# untitled.net
KiCad netlist of a schematic drawn in EAGLE
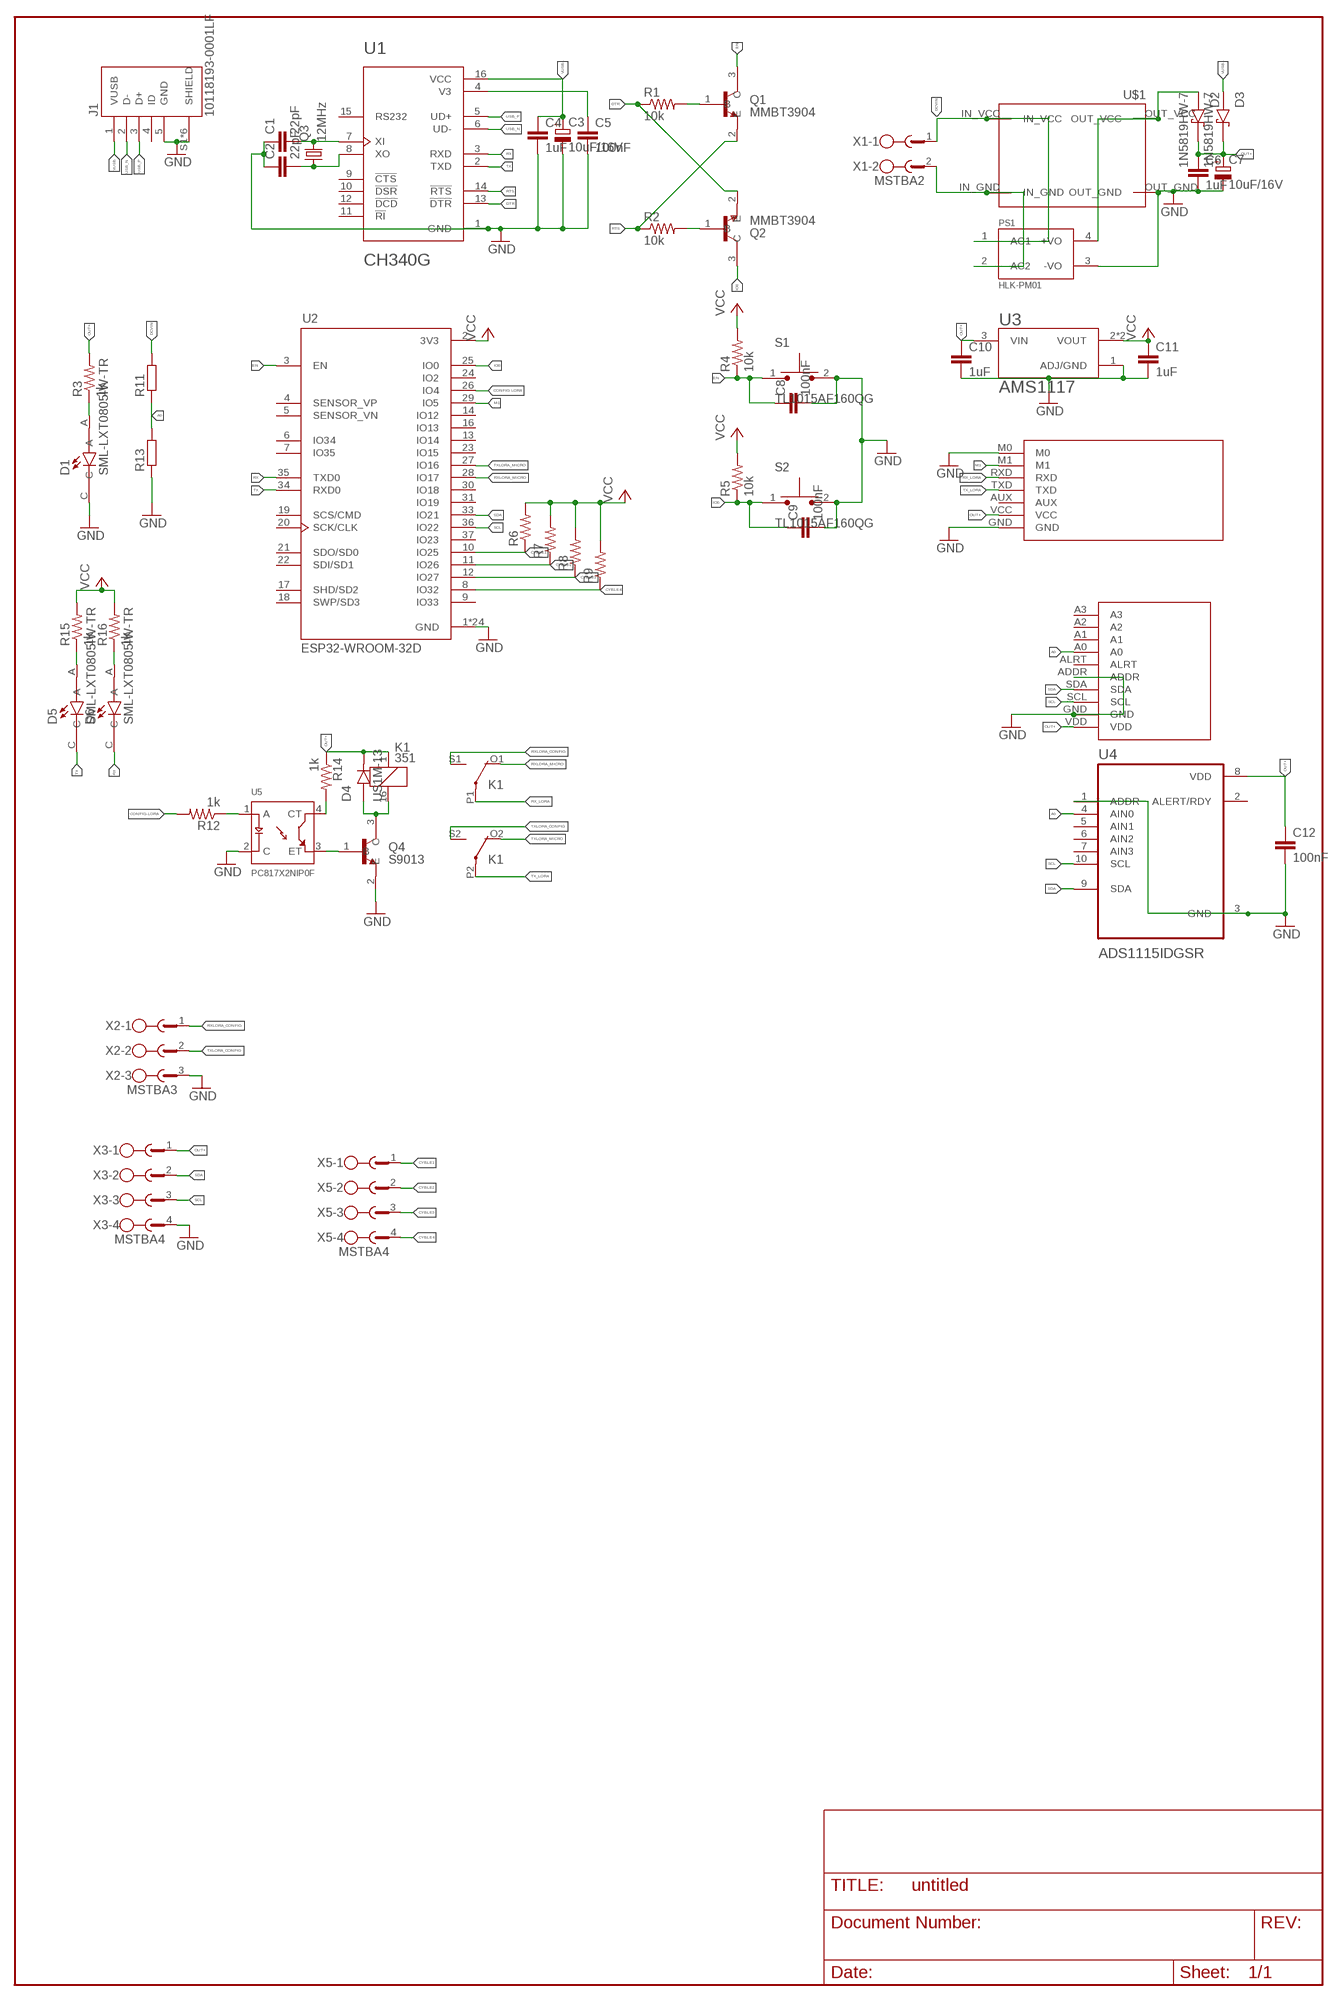
[diagram p0: schematic, sheet 1]

(export (version "E")
  (design (tool "Eeschema 10.0.6"))
  (components
    (comp (ref "ADS1")
      (value "ADS1115")
      (footprint "eagle-import:ADS1115")
      (libsource (lib "eagle-import") (part "ADS1115"))
    )
    (comp (ref "C1")
      (value "22pF")
      (footprint "eagle-import:C0805K")
      (libsource (lib "eagle-import") (part "C-EUC0805K"))
    )
    (comp (ref "C2")
      (value "22pF")
      (footprint "eagle-import:C0805K")
      (libsource (lib "eagle-import") (part "C-EUC0805K"))
    )
    (comp (ref "C3")
      (value "10uF/16V")
      (footprint "eagle-import:153CLV-0505")
      (libsource (lib "eagle-import") (part "CPOL-EU153CLV-0505"))
    )
    (comp (ref "C4")
      (value "1uF")
      (footprint "eagle-import:C0805K")
      (libsource (lib "eagle-import") (part "C-EUC0805K"))
    )
    (comp (ref "C5")
      (value "100nF")
      (footprint "eagle-import:C0805K")
      (libsource (lib "eagle-import") (part "C-EUC0805K"))
    )
    (comp (ref "C6")
      (value "1uF")
      (footprint "eagle-import:C0805K")
      (libsource (lib "eagle-import") (part "C-EUC0805K"))
    )
    (comp (ref "C7")
      (value "10uF/16V")
      (footprint "eagle-import:153CLV-0505")
      (libsource (lib "eagle-import") (part "CPOL-EU153CLV-0505"))
    )
    (comp (ref "C8")
      (value "100nF")
      (footprint "eagle-import:C0805K")
      (libsource (lib "eagle-import") (part "C-EUC0805K"))
    )
    (comp (ref "C9")
      (value "100nF")
      (footprint "eagle-import:C0805K")
      (libsource (lib "eagle-import") (part "C-EUC0805K"))
    )
    (comp (ref "C10")
      (value "1uF")
      (footprint "eagle-import:C0805K")
      (libsource (lib "eagle-import") (part "C-EUC0805K"))
    )
    (comp (ref "C11")
      (value "1uF")
      (footprint "eagle-import:C0805K")
      (libsource (lib "eagle-import") (part "C-EUC0805K"))
    )
    (comp (ref "C12")
      (value "100nF")
      (footprint "eagle-import:C0805K")
      (libsource (lib "eagle-import") (part "C-EUC0805K"))
    )
    (comp (ref "D1")
      (value "SML-LXT0805IW-TR")
      (footprint "eagle-import:LEDC2012X120N")
      (fields (field (name "MF") "Lumex Opto/Components"))
      (libsource (lib "eagle-import") (part "SML-LXT0805IW-TR"))
    )
    (comp (ref "D2")
      (value "1N5819HW-7")
      (footprint "eagle-import:SOD3715X145N")
      (fields (field (name "MF") "Diodes Inc."))
      (libsource (lib "eagle-import") (part "1N5819HW-7"))
    )
    (comp (ref "D3")
      (value "1N5819HW-7")
      (footprint "eagle-import:SOD3715X145N")
      (fields (field (name "MF") "Diodes Inc."))
      (libsource (lib "eagle-import") (part "1N5819HW-7"))
    )
    (comp (ref "D4")
      (value "US1M-13")
      (footprint "eagle-import:DIOM5226X240N")
      (fields (field (name "MF") "Diodes Incorporated"))
      (libsource (lib "eagle-import") (part "US1M-13"))
    )
    (comp (ref "D5")
      (value "SML-LXT0805IW-TR")
      (footprint "eagle-import:LEDC2012X120N")
      (fields (field (name "MF") "Lumex Opto/Components"))
      (libsource (lib "eagle-import") (part "SML-LXT0805IW-TR"))
    )
    (comp (ref "D6")
      (value "SML-LXT0805IW-TR")
      (footprint "eagle-import:LEDC2012X120N")
      (fields (field (name "MF") "Lumex Opto/Components"))
      (libsource (lib "eagle-import") (part "SML-LXT0805IW-TR"))
    )
    (comp (ref "EBYTEE220-900T22D1")
      (value "EBYTEE220-900T22D")
      (footprint "eagle-import:EBYTEE220-900T22D")
      (libsource (lib "eagle-import") (part "EBYTEE220-900T22D"))
    )
    (comp (ref "J1")
      (value "10118193-0001LF")
      (footprint "eagle-import:FCI_10118193-0001LF")
      (fields (field (name "MF") "FCI"))
      (libsource (lib "eagle-import") (part "10118193-0001LF"))
    )
    (comp (ref "K1")
      (value "351")
      (footprint "eagle-import:351")
      (libsource (lib "eagle-import") (part "351"))
    )
    (comp (ref "PS1")
      (value "HLK-PM01")
      (footprint "eagle-import:CONV_HLK-PM01")
      (fields (field (name "MF") "Hi-link") (field (name "MP") "hlk-pm01"))
      (libsource (lib "eagle-import") (part "HLK-PM01"))
    )
    (comp (ref "Q1")
      (value "MMBT3904")
      (footprint "eagle-import:SOT95P240X120-3N")
      (fields (field (name "MF") "ON Semiconductor"))
      (libsource (lib "eagle-import") (part "MMBT3904"))
    )
    (comp (ref "Q2")
      (value "MMBT3904")
      (footprint "eagle-import:SOT95P240X120-3N")
      (fields (field (name "MF") "ON Semiconductor"))
      (libsource (lib "eagle-import") (part "MMBT3904"))
    )
    (comp (ref "Q3")
      (value "12MHz")
      (footprint "eagle-import:SM49")
      (libsource (lib "eagle-import") (part "CRYSTALSM49"))
    )
    (comp (ref "Q4")
      (value "S9013")
      (footprint "eagle-import:SOT95P240X120-3N")
      (fields (field (name "MF") "JCET"))
      (libsource (lib "eagle-import") (part "S9013"))
    )
    (comp (ref "R1")
      (value "10k")
      (footprint "eagle-import:M0805")
      (libsource (lib "eagle-import") (part "R-US_M0805"))
    )
    (comp (ref "R2")
      (value "10k")
      (footprint "eagle-import:M0805")
      (libsource (lib "eagle-import") (part "R-US_M0805"))
    )
    (comp (ref "R3")
      (value "1k")
      (footprint "eagle-import:M0805")
      (libsource (lib "eagle-import") (part "R-US_M0805"))
    )
    (comp (ref "R4")
      (value "10k")
      (footprint "eagle-import:M0805")
      (libsource (lib "eagle-import") (part "R-US_M0805"))
    )
    (comp (ref "R5")
      (value "10k")
      (footprint "eagle-import:M0805")
      (libsource (lib "eagle-import") (part "R-US_M0805"))
    )
    (comp (ref "R6")
      (value "R-US_M0805")
      (footprint "eagle-import:M0805")
      (libsource (lib "eagle-import") (part "R-US_M0805"))
    )
    (comp (ref "R7")
      (value "R-US_M0805")
      (footprint "eagle-import:M0805")
      (libsource (lib "eagle-import") (part "R-US_M0805"))
    )
    (comp (ref "R8")
      (value "R-US_M0805")
      (footprint "eagle-import:M0805")
      (libsource (lib "eagle-import") (part "R-US_M0805"))
    )
    (comp (ref "R9")
      (value "R-US_M0805")
      (footprint "eagle-import:M0805")
      (libsource (lib "eagle-import") (part "R-US_M0805"))
    )
    (comp (ref "R11")
      (value "R-EU_0207/12")
      (footprint "eagle-import:0207_12")
      (libsource (lib "eagle-import") (part "R-EU_0207/12"))
    )
    (comp (ref "R12")
      (value "1k")
      (footprint "eagle-import:M0805")
      (libsource (lib "eagle-import") (part "R-US_M0805"))
    )
    (comp (ref "R13")
      (value "R-EU_0207/12")
      (footprint "eagle-import:0207_12")
      (libsource (lib "eagle-import") (part "R-EU_0207/12"))
    )
    (comp (ref "R14")
      (value "1k")
      (footprint "eagle-import:M0805")
      (libsource (lib "eagle-import") (part "R-US_M0805"))
    )
    (comp (ref "R15")
      (value "1k")
      (footprint "eagle-import:M0805")
      (libsource (lib "eagle-import") (part "R-US_M0805"))
    )
    (comp (ref "R16")
      (value "1k")
      (footprint "eagle-import:M0805")
      (libsource (lib "eagle-import") (part "R-US_M0805"))
    )
    (comp (ref "S1")
      (value "TL1015AF160QG")
      (footprint "eagle-import:SW_TL1015AF160QG")
      (fields (field (name "MF") "E-Switch"))
      (libsource (lib "eagle-import") (part "TL1015AF160QG"))
    )
    (comp (ref "S2")
      (value "TL1015AF160QG")
      (footprint "eagle-import:SW_TL1015AF160QG")
      (fields (field (name "MF") "E-Switch"))
      (libsource (lib "eagle-import") (part "TL1015AF160QG"))
    )
    (comp (ref "U$1")
      (value "STEPDOWN_SY8205")
      (footprint "eagle-import:STEPDOWN_SY8205")
      (libsource (lib "eagle-import") (part "STEPDOWN_SY8205"))
    )
    (comp (ref "U1")
      (value "CH340G")
      (footprint "eagle-import:SOIC127P600X180-16N")
      (fields (field (name "MF") "WCH") (field (name "MP") "Ch340G"))
      (libsource (lib "eagle-import") (part "CH340G"))
    )
    (comp (ref "U2")
      (value "ESP32-WROOM-32D")
      (footprint "eagle-import:MODULE_ESP32-WROOM-32D")
      (fields (field (name "MF") "Espressif Systems"))
      (libsource (lib "eagle-import") (part "ESP32-WROOM-32D"))
    )
    (comp (ref "U3")
      (value "AMS1117")
      (footprint "eagle-import:SOT229P700X180-4N")
      (fields (field (name "MF") "Advanced Monolithic Systems"))
      (libsource (lib "eagle-import") (part "AMS1117"))
    )
    (comp (ref "U4")
      (value "ADS1115IDGSR")
      (footprint "eagle-import:SOP50P490X110-10N")
      (fields (field (name "MF") "Texas Instruments"))
      (libsource (lib "eagle-import") (part "ADS1115IDGSR"))
    )
    (comp (ref "U5")
      (value "PC817X2NIP0F")
      (footprint "eagle-import:SOT254P975X400-4N")
      (fields (field (name "MF") "Sharp Microelectronics"))
      (libsource (lib "eagle-import") (part "PC817X2NIP0F"))
    )
    (comp (ref "X1")
      (value "MSTBA2")
      (footprint "eagle-import:MSTBA2")
      (fields (field (name "MF") "FARNELL") (field (name "MPN") "1757242"))
      (libsource (lib "eagle-import") (part "MSTBA2"))
    )
    (comp (ref "X2")
      (value "MSTBA3")
      (footprint "eagle-import:MSTBA3")
      (fields (field (name "MF") "FARNELL") (field (name "MPN") "1757255"))
      (libsource (lib "eagle-import") (part "MSTBA3"))
    )
    (comp (ref "X3")
      (value "MSTBA4")
      (footprint "eagle-import:MSTBA4")
      (fields (field (name "MF") "FARNELL") (field (name "MPN") "1757268"))
      (libsource (lib "eagle-import") (part "MSTBA4"))
    )
    (comp (ref "X5")
      (value "MSTBA4")
      (footprint "eagle-import:MSTBA4")
      (fields (field (name "MF") "FARNELL") (field (name "MPN") "1757268"))
      (libsource (lib "eagle-import") (part "MSTBA4"))
    )
  )
  (nets
    (net (code "1") (name "A0") (class "Default")
      (node (ref "ADS1") (pin "A0") (pinfunction "A0_A0") (pintype "bidirectional"))
      (node (ref "R11") (pin "1") (pinfunction "1_1") (pintype "passive"))
      (node (ref "R13") (pin "2") (pinfunction "2_2") (pintype "passive"))
      (node (ref "U4") (pin "4") (pinfunction "AIN0_4") (pintype "input"))
    )
    (net (code "2") (name "CONFIG-LORA") (class "Default")
      (node (ref "R12") (pin "2") (pinfunction "2_2") (pintype "passive"))
      (node (ref "U2") (pin "26") (pinfunction "IO4_26") (pintype "bidirectional"))
    )
    (net (code "3") (name "CYBLE1") (class "Default")
      (node (ref "R6") (pin "1") (pinfunction "1_1") (pintype "passive"))
      (node (ref "U2") (pin "10") (pinfunction "IO25_10") (pintype "bidirectional"))
      (node (ref "X5") (pin "1") (pinfunction "1_1") (pintype "passive"))
    )
    (net (code "4") (name "CYBLE2") (class "Default")
      (node (ref "R7") (pin "1") (pinfunction "1_1") (pintype "passive"))
      (node (ref "U2") (pin "11") (pinfunction "IO26_11") (pintype "bidirectional"))
      (node (ref "X5") (pin "2") (pinfunction "1_2") (pintype "passive"))
    )
    (net (code "5") (name "CYBLE3") (class "Default")
      (node (ref "R8") (pin "1") (pinfunction "1_1") (pintype "passive"))
      (node (ref "U2") (pin "12") (pinfunction "IO27_12") (pintype "bidirectional"))
      (node (ref "X5") (pin "3") (pinfunction "1_3") (pintype "passive"))
    )
    (net (code "6") (name "CYBLE4") (class "Default")
      (node (ref "R9") (pin "1") (pinfunction "1_1") (pintype "passive"))
      (node (ref "U2") (pin "8") (pinfunction "IO32_8") (pintype "bidirectional"))
      (node (ref "X5") (pin "4") (pinfunction "1_4") (pintype "passive"))
    )
    (net (code "7") (name "DCVIN") (class "Default")
      (node (ref "PS1") (pin "1") (pinfunction "AC1_1") (pintype "input"))
      (node (ref "R11") (pin "2") (pinfunction "2_2") (pintype "passive"))
      (node (ref "U$1") (pin "IN_VCC") (pinfunction "IN_VCC_IN_VCC") (pintype "bidirectional"))
      (node (ref "X1") (pin "1") (pinfunction "1_1") (pintype "passive"))
    )
    (net (code "8") (name "DTR") (class "Default")
      (node (ref "Q2") (pin "2") (pinfunction "E_2") (pintype "passive"))
      (node (ref "R1") (pin "1") (pinfunction "1_1") (pintype "passive"))
      (node (ref "U1") (pin "13") (pinfunction "~{DTR}_13") (pintype "output"))
    )
    (net (code "9") (name "EN") (class "Default")
      (node (ref "C8") (pin "1") (pinfunction "1_1") (pintype "passive"))
      (node (ref "Q1") (pin "3") (pinfunction "C_3") (pintype "passive"))
      (node (ref "R4") (pin "1") (pinfunction "1_1") (pintype "passive"))
      (node (ref "S1") (pin "1") (pinfunction "1_1") (pintype "passive"))
      (node (ref "U2") (pin "3") (pinfunction "EN_3") (pintype "input"))
    )
    (net (code "10") (name "GND") (class "Default")
      (node (ref "ADS1") (pin "ADDR") (pinfunction "ADDR_ADDR") (pintype "bidirectional"))
      (node (ref "ADS1") (pin "GND") (pinfunction "GND_GND") (pintype "bidirectional"))
      (node (ref "C1") (pin "1") (pinfunction "1_1") (pintype "passive"))
      (node (ref "C10") (pin "2") (pinfunction "2_2") (pintype "passive"))
      (node (ref "C11") (pin "2") (pinfunction "2_2") (pintype "passive"))
      (node (ref "C12") (pin "2") (pinfunction "2_2") (pintype "passive"))
      (node (ref "C2") (pin "1") (pinfunction "1_1") (pintype "passive"))
      (node (ref "C3") (pin "-") (pinfunction "-_-") (pintype "passive"))
      (node (ref "C4") (pin "2") (pinfunction "2_2") (pintype "passive"))
      (node (ref "C5") (pin "2") (pinfunction "2_2") (pintype "passive"))
      (node (ref "C6") (pin "2") (pinfunction "2_2") (pintype "passive"))
      (node (ref "C7") (pin "-") (pinfunction "-_-") (pintype "passive"))
      (node (ref "C8") (pin "2") (pinfunction "2_2") (pintype "passive"))
      (node (ref "C9") (pin "2") (pinfunction "2_2") (pintype "passive"))
      (node (ref "D1") (pin "C") (pinfunction "C_C") (pintype "passive"))
      (node (ref "EBYTEE220-900T22D1") (pin "GND") (pinfunction "GND_GND") (pintype "bidirectional"))
      (node (ref "EBYTEE220-900T22D1") (pin "M0") (pinfunction "M0_M0") (pintype "bidirectional"))
      (node (ref "J1") (pin "5") (pinfunction "GND_5") (pintype "passive"))
      (node (ref "J1") (pin "S1") (pinfunction "SHIELD_S1") (pintype "passive"))
      (node (ref "J1") (pin "S2") (pinfunction "SHIELD_S2") (pintype "passive"))
      (node (ref "J1") (pin "S3") (pinfunction "SHIELD_S3") (pintype "passive"))
      (node (ref "J1") (pin "S4") (pinfunction "SHIELD_S4") (pintype "passive"))
      (node (ref "J1") (pin "S5") (pinfunction "SHIELD_S5") (pintype "passive"))
      (node (ref "J1") (pin "S6") (pinfunction "SHIELD_S6") (pintype "passive"))
      (node (ref "PS1") (pin "3") (pinfunction "-VO_3") (pintype "output"))
      (node (ref "Q4") (pin "2") (pinfunction "E_2") (pintype "passive"))
      (node (ref "R13") (pin "1") (pinfunction "1_1") (pintype "passive"))
      (node (ref "S1") (pin "2") (pinfunction "2_2") (pintype "passive"))
      (node (ref "S2") (pin "2") (pinfunction "2_2") (pintype "passive"))
      (node (ref "U$1") (pin "OUT_GND") (pinfunction "OUT_GND_OUT_GND") (pintype "bidirectional"))
      (node (ref "U1") (pin "1") (pinfunction "GND_1") (pintype "power_in"))
      (node (ref "U2") (pin "1") (pinfunction "GND_1") (pintype "power_in"))
      (node (ref "U2") (pin "15") (pinfunction "GND_15") (pintype "power_in"))
      (node (ref "U2") (pin "38") (pinfunction "GND_38") (pintype "power_in"))
      (node (ref "U2") (pin "39_1") (pinfunction "GND_39_1") (pintype "power_in"))
      (node (ref "U2") (pin "39_10") (pinfunction "GND_39_10") (pintype "power_in"))
      (node (ref "U2") (pin "39_11") (pinfunction "GND_39_11") (pintype "power_in"))
      (node (ref "U2") (pin "39_12") (pinfunction "GND_39_12") (pintype "power_in"))
      (node (ref "U2") (pin "39_13") (pinfunction "GND_39_13") (pintype "power_in"))
      (node (ref "U2") (pin "39_14") (pinfunction "GND_39_14") (pintype "power_in"))
      (node (ref "U2") (pin "39_15") (pinfunction "GND_39_15") (pintype "power_in"))
      (node (ref "U2") (pin "39_16") (pinfunction "GND_39_16") (pintype "power_in"))
      (node (ref "U2") (pin "39_17") (pinfunction "GND_39_17") (pintype "power_in"))
      (node (ref "U2") (pin "39_18") (pinfunction "GND_39_18") (pintype "power_in"))
      (node (ref "U2") (pin "39_19") (pinfunction "GND_39_19") (pintype "power_in"))
      (node (ref "U2") (pin "39_2") (pinfunction "GND_39_2") (pintype "power_in"))
      (node (ref "U2") (pin "39_20") (pinfunction "GND_39_20") (pintype "power_in"))
      (node (ref "U2") (pin "39_21") (pinfunction "GND_39_21") (pintype "power_in"))
      (node (ref "U2") (pin "39_3") (pinfunction "GND_39_3") (pintype "power_in"))
      (node (ref "U2") (pin "39_4") (pinfunction "GND_39_4") (pintype "power_in"))
      (node (ref "U2") (pin "39_5") (pinfunction "GND_39_5") (pintype "power_in"))
      (node (ref "U2") (pin "39_6") (pinfunction "GND_39_6") (pintype "power_in"))
      (node (ref "U2") (pin "39_7") (pinfunction "GND_39_7") (pintype "power_in"))
      (node (ref "U2") (pin "39_8") (pinfunction "GND_39_8") (pintype "power_in"))
      (node (ref "U2") (pin "39_9") (pinfunction "GND_39_9") (pintype "power_in"))
      (node (ref "U3") (pin "1") (pinfunction "ADJ/GND_1") (pintype "power_in"))
      (node (ref "U4") (pin "1") (pinfunction "ADDR_1") (pintype "input"))
      (node (ref "U4") (pin "3") (pinfunction "GND_3") (pintype "power_in"))
      (node (ref "U5") (pin "2") (pinfunction "C_2") (pintype "passive"))
      (node (ref "X2") (pin "3") (pinfunction "1_3") (pintype "passive"))
      (node (ref "X3") (pin "4") (pinfunction "1_4") (pintype "passive"))
    )
    (net (code "11") (name "IO0") (class "Default")
      (node (ref "C9") (pin "1") (pinfunction "1_1") (pintype "passive"))
      (node (ref "Q2") (pin "3") (pinfunction "C_3") (pintype "passive"))
      (node (ref "R5") (pin "1") (pinfunction "1_1") (pintype "passive"))
      (node (ref "S2") (pin "1") (pinfunction "1_1") (pintype "passive"))
      (node (ref "U2") (pin "25") (pinfunction "IO0_25") (pintype "bidirectional"))
    )
    (net (code "12") (name "M1") (class "Default")
      (node (ref "EBYTEE220-900T22D1") (pin "M1") (pinfunction "M1_M1") (pintype "bidirectional"))
      (node (ref "U2") (pin "29") (pinfunction "IO5_29") (pintype "bidirectional"))
    )
    (net (code "13") (name "Net-(D1-PadA)") (class "Default")
      (node (ref "D1") (pin "A") (pinfunction "A_A") (pintype "passive"))
      (node (ref "R3") (pin "1") (pinfunction "1_1") (pintype "passive"))
    )
    (net (code "14") (name "Net-(D5-PadA)") (class "Default")
      (node (ref "D5") (pin "A") (pinfunction "A_A") (pintype "passive"))
      (node (ref "R15") (pin "1") (pinfunction "1_1") (pintype "passive"))
    )
    (net (code "15") (name "Net-(D6-PadA)") (class "Default")
      (node (ref "D6") (pin "A") (pinfunction "A_A") (pintype "passive"))
      (node (ref "R16") (pin "1") (pinfunction "1_1") (pintype "passive"))
    )
    (net (code "16") (name "Net-(K1A-2)") (class "Default")
      (node (ref "D4") (pin "A") (pinfunction "A_A") (pintype "passive"))
      (node (ref "K1") (pin "16") (pinfunction "2_16") (pintype "passive"))
      (node (ref "Q4") (pin "3") (pinfunction "C_3") (pintype "passive"))
    )
    (net (code "17") (name "Net-(PS1-+VO)") (class "Default")
      (node (ref "D2") (pin "A") (pinfunction "A_A") (pintype "passive"))
      (node (ref "PS1") (pin "4") (pinfunction "+VO_4") (pintype "output"))
      (node (ref "U$1") (pin "OUT_VCC") (pinfunction "OUT_VCC_OUT_VCC") (pintype "bidirectional"))
    )
    (net (code "18") (name "Net-(PS1-AC2)") (class "Default")
      (node (ref "PS1") (pin "2") (pinfunction "AC2_2") (pintype "input"))
      (node (ref "U$1") (pin "IN_GND") (pinfunction "IN_GND_IN_GND") (pintype "bidirectional"))
      (node (ref "X1") (pin "2") (pinfunction "1_2") (pintype "passive"))
    )
    (net (code "19") (name "Net-(Q1-B)") (class "Default")
      (node (ref "Q1") (pin "1") (pinfunction "B_1") (pintype "passive"))
      (node (ref "R1") (pin "2") (pinfunction "2_2") (pintype "passive"))
    )
    (net (code "20") (name "Net-(Q2-B)") (class "Default")
      (node (ref "Q2") (pin "1") (pinfunction "B_1") (pintype "passive"))
      (node (ref "R2") (pin "2") (pinfunction "2_2") (pintype "passive"))
    )
    (net (code "21") (name "Net-(Q4-B)") (class "Default")
      (node (ref "Q4") (pin "1") (pinfunction "B_1") (pintype "passive"))
      (node (ref "U5") (pin "3") (pinfunction "ET_3") (pintype "passive"))
    )
    (net (code "22") (name "Net-(U1-V3)") (class "Default")
      (node (ref "C5") (pin "1") (pinfunction "1_1") (pintype "passive"))
      (node (ref "U1") (pin "4") (pinfunction "V3_4") (pintype "power_in"))
    )
    (net (code "23") (name "Net-(U1-XI)") (class "Default")
      (node (ref "C1") (pin "2") (pinfunction "2_2") (pintype "passive"))
      (node (ref "Q3") (pin "2") (pinfunction "2_2") (pintype "passive"))
      (node (ref "U1") (pin "7") (pinfunction "XI_7") (pintype "input"))
    )
    (net (code "24") (name "Net-(U1-XO)") (class "Default")
      (node (ref "C2") (pin "2") (pinfunction "2_2") (pintype "passive"))
      (node (ref "Q3") (pin "1") (pinfunction "1_1") (pintype "passive"))
      (node (ref "U1") (pin "8") (pinfunction "XO_8") (pintype "output"))
    )
    (net (code "25") (name "Net-(U5-A)") (class "Default")
      (node (ref "R12") (pin "1") (pinfunction "1_1") (pintype "passive"))
      (node (ref "U5") (pin "1") (pinfunction "A_1") (pintype "passive"))
    )
    (net (code "26") (name "Net-(U5-CT)") (class "Default")
      (node (ref "R14") (pin "2") (pinfunction "2_2") (pintype "passive"))
      (node (ref "U5") (pin "4") (pinfunction "CT_4") (pintype "passive"))
    )
    (net (code "27") (name "OUT+") (class "Default")
      (node (ref "ADS1") (pin "VDD") (pinfunction "VDD_VDD") (pintype "bidirectional"))
      (node (ref "C10") (pin "1") (pinfunction "1_1") (pintype "passive"))
      (node (ref "C12") (pin "1") (pinfunction "1_1") (pintype "passive"))
      (node (ref "C6") (pin "1") (pinfunction "1_1") (pintype "passive"))
      (node (ref "C7") (pin "+") (pinfunction "+_+") (pintype "passive"))
      (node (ref "D2") (pin "C") (pinfunction "K_C") (pintype "passive"))
      (node (ref "D3") (pin "C") (pinfunction "K_C") (pintype "passive"))
      (node (ref "D4") (pin "C") (pinfunction "K_C") (pintype "passive"))
      (node (ref "EBYTEE220-900T22D1") (pin "VCC") (pinfunction "VCC_VCC") (pintype "bidirectional"))
      (node (ref "K1") (pin "1") (pinfunction "1_1") (pintype "passive"))
      (node (ref "R14") (pin "1") (pinfunction "1_1") (pintype "passive"))
      (node (ref "R3") (pin "2") (pinfunction "2_2") (pintype "passive"))
      (node (ref "U3") (pin "3") (pinfunction "VIN_3") (pintype "input"))
      (node (ref "U4") (pin "8") (pinfunction "VDD_8") (pintype "power_in"))
      (node (ref "X3") (pin "1") (pinfunction "1_1") (pintype "passive"))
    )
    (net (code "28") (name "RTS") (class "Default")
      (node (ref "Q1") (pin "2") (pinfunction "E_2") (pintype "passive"))
      (node (ref "R2") (pin "1") (pinfunction "1_1") (pintype "passive"))
      (node (ref "U1") (pin "14") (pinfunction "~{RTS}_14") (pintype "output"))
    )
    (net (code "29") (name "RX") (class "Default")
      (node (ref "D6") (pin "C") (pinfunction "C_C") (pintype "passive"))
      (node (ref "U1") (pin "3") (pinfunction "RXD_3") (pintype "input"))
      (node (ref "U2") (pin "35") (pinfunction "TXD0_35") (pintype "bidirectional"))
    )
    (net (code "30") (name "RXLORA_CONFIG") (class "Default")
      (node (ref "K1") (pin "S1") (pinfunction "S_S1") (pintype "passive"))
      (node (ref "X2") (pin "1") (pinfunction "1_1") (pintype "passive"))
    )
    (net (code "31") (name "RXLORA_MICRO") (class "Default")
      (node (ref "K1") (pin "O1") (pinfunction "O_O1") (pintype "passive"))
      (node (ref "U2") (pin "28") (pinfunction "IO17_28") (pintype "bidirectional"))
    )
    (net (code "32") (name "RX_LORA") (class "Default")
      (node (ref "EBYTEE220-900T22D1") (pin "RXD") (pinfunction "RXD_RXD") (pintype "bidirectional"))
      (node (ref "K1") (pin "P1") (pinfunction "P_P1") (pintype "passive"))
    )
    (net (code "33") (name "SCL") (class "Default")
      (node (ref "ADS1") (pin "SCL") (pinfunction "SCL_SCL") (pintype "bidirectional"))
      (node (ref "U2") (pin "36") (pinfunction "IO22_36") (pintype "bidirectional"))
      (node (ref "U4") (pin "10") (pinfunction "SCL_10") (pintype "input"))
      (node (ref "X3") (pin "3") (pinfunction "1_3") (pintype "passive"))
    )
    (net (code "34") (name "SDA") (class "Default")
      (node (ref "ADS1") (pin "SDA") (pinfunction "SDA_SDA") (pintype "bidirectional"))
      (node (ref "U2") (pin "33") (pinfunction "IO21_33") (pintype "bidirectional"))
      (node (ref "U4") (pin "9") (pinfunction "SDA_9") (pintype "bidirectional"))
      (node (ref "X3") (pin "2") (pinfunction "1_2") (pintype "passive"))
    )
    (net (code "35") (name "TX") (class "Default")
      (node (ref "D5") (pin "C") (pinfunction "C_C") (pintype "passive"))
      (node (ref "U1") (pin "2") (pinfunction "TXD_2") (pintype "output"))
      (node (ref "U2") (pin "34") (pinfunction "RXD0_34") (pintype "bidirectional"))
    )
    (net (code "36") (name "TXLORA_CONFIG") (class "Default")
      (node (ref "K1") (pin "S2") (pinfunction "S_S2") (pintype "passive"))
      (node (ref "X2") (pin "2") (pinfunction "1_2") (pintype "passive"))
    )
    (net (code "37") (name "TXLORA_MICRO") (class "Default")
      (node (ref "K1") (pin "O2") (pinfunction "O_O2") (pintype "passive"))
      (node (ref "U2") (pin "27") (pinfunction "IO16_27") (pintype "bidirectional"))
    )
    (net (code "38") (name "TX_LORA") (class "Default")
      (node (ref "EBYTEE220-900T22D1") (pin "TXD") (pinfunction "TXD_TXD") (pintype "bidirectional"))
      (node (ref "K1") (pin "P2") (pinfunction "P_P2") (pintype "passive"))
    )
    (net (code "39") (name "USB_N") (class "Default")
      (node (ref "J1") (pin "2") (pinfunction "D-_2") (pintype "passive"))
      (node (ref "U1") (pin "6") (pinfunction "UD-_6") (pintype "bidirectional"))
    )
    (net (code "40") (name "USB_P") (class "Default")
      (node (ref "J1") (pin "3") (pinfunction "D+_3") (pintype "passive"))
      (node (ref "U1") (pin "5") (pinfunction "UD+_5") (pintype "bidirectional"))
    )
    (net (code "41") (name "VCC") (class "Default")
      (node (ref "C11") (pin "1") (pinfunction "1_1") (pintype "passive"))
      (node (ref "R15") (pin "2") (pinfunction "2_2") (pintype "passive"))
      (node (ref "R16") (pin "2") (pinfunction "2_2") (pintype "passive"))
      (node (ref "R4") (pin "2") (pinfunction "2_2") (pintype "passive"))
      (node (ref "R5") (pin "2") (pinfunction "2_2") (pintype "passive"))
      (node (ref "R6") (pin "2") (pinfunction "2_2") (pintype "passive"))
      (node (ref "R7") (pin "2") (pinfunction "2_2") (pintype "passive"))
      (node (ref "R8") (pin "2") (pinfunction "2_2") (pintype "passive"))
      (node (ref "R9") (pin "2") (pinfunction "2_2") (pintype "passive"))
      (node (ref "U2") (pin "2") (pinfunction "3V3_2") (pintype "power_in"))
      (node (ref "U3") (pin "2") (pinfunction "VOUT_2") (pintype "output"))
      (node (ref "U3") (pin "4") (pinfunction "VOUT_4") (pintype "output"))
    )
    (net (code "42") (name "VUSB") (class "Default")
      (node (ref "C3") (pin "+") (pinfunction "+_+") (pintype "passive"))
      (node (ref "C4") (pin "1") (pinfunction "1_1") (pintype "passive"))
      (node (ref "D3") (pin "A") (pinfunction "A_A") (pintype "passive"))
      (node (ref "J1") (pin "1") (pinfunction "VUSB_1") (pintype "passive"))
      (node (ref "U1") (pin "16") (pinfunction "VCC_16") (pintype "power_in"))
    )
    (net (code "43") (name "unconnected-(ADS1-PadA1)") (class "Default")
      (node (ref "ADS1") (pin "A1") (pinfunction "A1_A1") (pintype "bidirectional"))
    )
    (net (code "44") (name "unconnected-(ADS1-PadA2)") (class "Default")
      (node (ref "ADS1") (pin "A2") (pinfunction "A2_A2") (pintype "bidirectional"))
    )
    (net (code "45") (name "unconnected-(ADS1-PadA3)") (class "Default")
      (node (ref "ADS1") (pin "A3") (pinfunction "A3_A3") (pintype "bidirectional"))
    )
    (net (code "46") (name "unconnected-(ADS1-PadALRT)") (class "Default")
      (node (ref "ADS1") (pin "ALRT") (pinfunction "ALRT_ALRT") (pintype "bidirectional"))
    )
    (net (code "47") (name "unconnected-(EBYTEE220-900T22D1-PadAUX)") (class "Default")
      (node (ref "EBYTEE220-900T22D1") (pin "AUX") (pinfunction "AUX_AUX") (pintype "bidirectional"))
    )
    (net (code "48") (name "unconnected-(J1-ID-Pad4)") (class "Default")
      (node (ref "J1") (pin "4") (pinfunction "ID_4") (pintype "passive"))
    )
    (net (code "49") (name "unconnected-(U1-RS232-Pad15)") (class "Default")
      (node (ref "U1") (pin "15") (pinfunction "RS232_15") (pintype "input"))
    )
    (net (code "50") (name "unconnected-(U1-~{CTS}-Pad9)") (class "Default")
      (node (ref "U1") (pin "9") (pinfunction "~{CTS}_9") (pintype "input"))
    )
    (net (code "51") (name "unconnected-(U1-~{DCD}-Pad12)") (class "Default")
      (node (ref "U1") (pin "12") (pinfunction "~{DCD}_12") (pintype "input"))
    )
    (net (code "52") (name "unconnected-(U1-~{DSR}-Pad10)") (class "Default")
      (node (ref "U1") (pin "10") (pinfunction "~{DSR}_10") (pintype "input"))
    )
    (net (code "53") (name "unconnected-(U1-~{RI}-Pad11)") (class "Default")
      (node (ref "U1") (pin "11") (pinfunction "~{RI}_11") (pintype "input"))
    )
    (net (code "54") (name "unconnected-(U2-IO2-Pad24)") (class "Default")
      (node (ref "U2") (pin "24") (pinfunction "IO2_24") (pintype "bidirectional"))
    )
    (net (code "55") (name "unconnected-(U2-IO12-Pad14)") (class "Default")
      (node (ref "U2") (pin "14") (pinfunction "IO12_14") (pintype "bidirectional"))
    )
    (net (code "56") (name "unconnected-(U2-IO13-Pad16)") (class "Default")
      (node (ref "U2") (pin "16") (pinfunction "IO13_16") (pintype "bidirectional"))
    )
    (net (code "57") (name "unconnected-(U2-IO14-Pad13)") (class "Default")
      (node (ref "U2") (pin "13") (pinfunction "IO14_13") (pintype "bidirectional"))
    )
    (net (code "58") (name "unconnected-(U2-IO15-Pad23)") (class "Default")
      (node (ref "U2") (pin "23") (pinfunction "IO15_23") (pintype "bidirectional"))
    )
    (net (code "59") (name "unconnected-(U2-IO18-Pad30)") (class "Default")
      (node (ref "U2") (pin "30") (pinfunction "IO18_30") (pintype "bidirectional"))
    )
    (net (code "60") (name "unconnected-(U2-IO19-Pad31)") (class "Default")
      (node (ref "U2") (pin "31") (pinfunction "IO19_31") (pintype "bidirectional"))
    )
    (net (code "61") (name "unconnected-(U2-IO23-Pad37)") (class "Default")
      (node (ref "U2") (pin "37") (pinfunction "IO23_37") (pintype "bidirectional"))
    )
    (net (code "62") (name "unconnected-(U2-IO33-Pad9)") (class "Default")
      (node (ref "U2") (pin "9") (pinfunction "IO33_9") (pintype "bidirectional"))
    )
    (net (code "63") (name "unconnected-(U2-IO34-Pad6)") (class "Default")
      (node (ref "U2") (pin "6") (pinfunction "IO34_6") (pintype "input"))
    )
    (net (code "64") (name "unconnected-(U2-IO35-Pad7)") (class "Default")
      (node (ref "U2") (pin "7") (pinfunction "IO35_7") (pintype "input"))
    )
    (net (code "65") (name "unconnected-(U2-SCK{slash}CLK-Pad20)") (class "Default")
      (node (ref "U2") (pin "20") (pinfunction "SCK/CLK_20") (pintype "bidirectional"))
    )
    (net (code "66") (name "unconnected-(U2-SCS{slash}CMD-Pad19)") (class "Default")
      (node (ref "U2") (pin "19") (pinfunction "SCS/CMD_19") (pintype "bidirectional"))
    )
    (net (code "67") (name "unconnected-(U2-SDI{slash}SD1-Pad22)") (class "Default")
      (node (ref "U2") (pin "22") (pinfunction "SDI/SD1_22") (pintype "bidirectional"))
    )
    (net (code "68") (name "unconnected-(U2-SDO{slash}SD0-Pad21)") (class "Default")
      (node (ref "U2") (pin "21") (pinfunction "SDO/SD0_21") (pintype "bidirectional"))
    )
    (net (code "69") (name "unconnected-(U2-SENSOR_VN-Pad5)") (class "Default")
      (node (ref "U2") (pin "5") (pinfunction "SENSOR_VN_5") (pintype "input"))
    )
    (net (code "70") (name "unconnected-(U2-SENSOR_VP-Pad4)") (class "Default")
      (node (ref "U2") (pin "4") (pinfunction "SENSOR_VP_4") (pintype "input"))
    )
    (net (code "71") (name "unconnected-(U2-SHD{slash}SD2-Pad17)") (class "Default")
      (node (ref "U2") (pin "17") (pinfunction "SHD/SD2_17") (pintype "bidirectional"))
    )
    (net (code "72") (name "unconnected-(U2-SWP{slash}SD3-Pad18)") (class "Default")
      (node (ref "U2") (pin "18") (pinfunction "SWP/SD3_18") (pintype "bidirectional"))
    )
    (net (code "73") (name "unconnected-(U4-AIN1-Pad5)") (class "Default")
      (node (ref "U4") (pin "5") (pinfunction "AIN1_5") (pintype "input"))
    )
    (net (code "74") (name "unconnected-(U4-AIN2-Pad6)") (class "Default")
      (node (ref "U4") (pin "6") (pinfunction "AIN2_6") (pintype "input"))
    )
    (net (code "75") (name "unconnected-(U4-AIN3-Pad7)") (class "Default")
      (node (ref "U4") (pin "7") (pinfunction "AIN3_7") (pintype "input"))
    )
    (net (code "76") (name "unconnected-(U4-ALERT{slash}RDY-Pad2)") (class "Default")
      (node (ref "U4") (pin "2") (pinfunction "ALERT/RDY_2") (pintype "output"))
    )
  )
)
